# 04_HV_Bus_Sense.net
KiCad netlist of a schematic drawn in Altium Designer
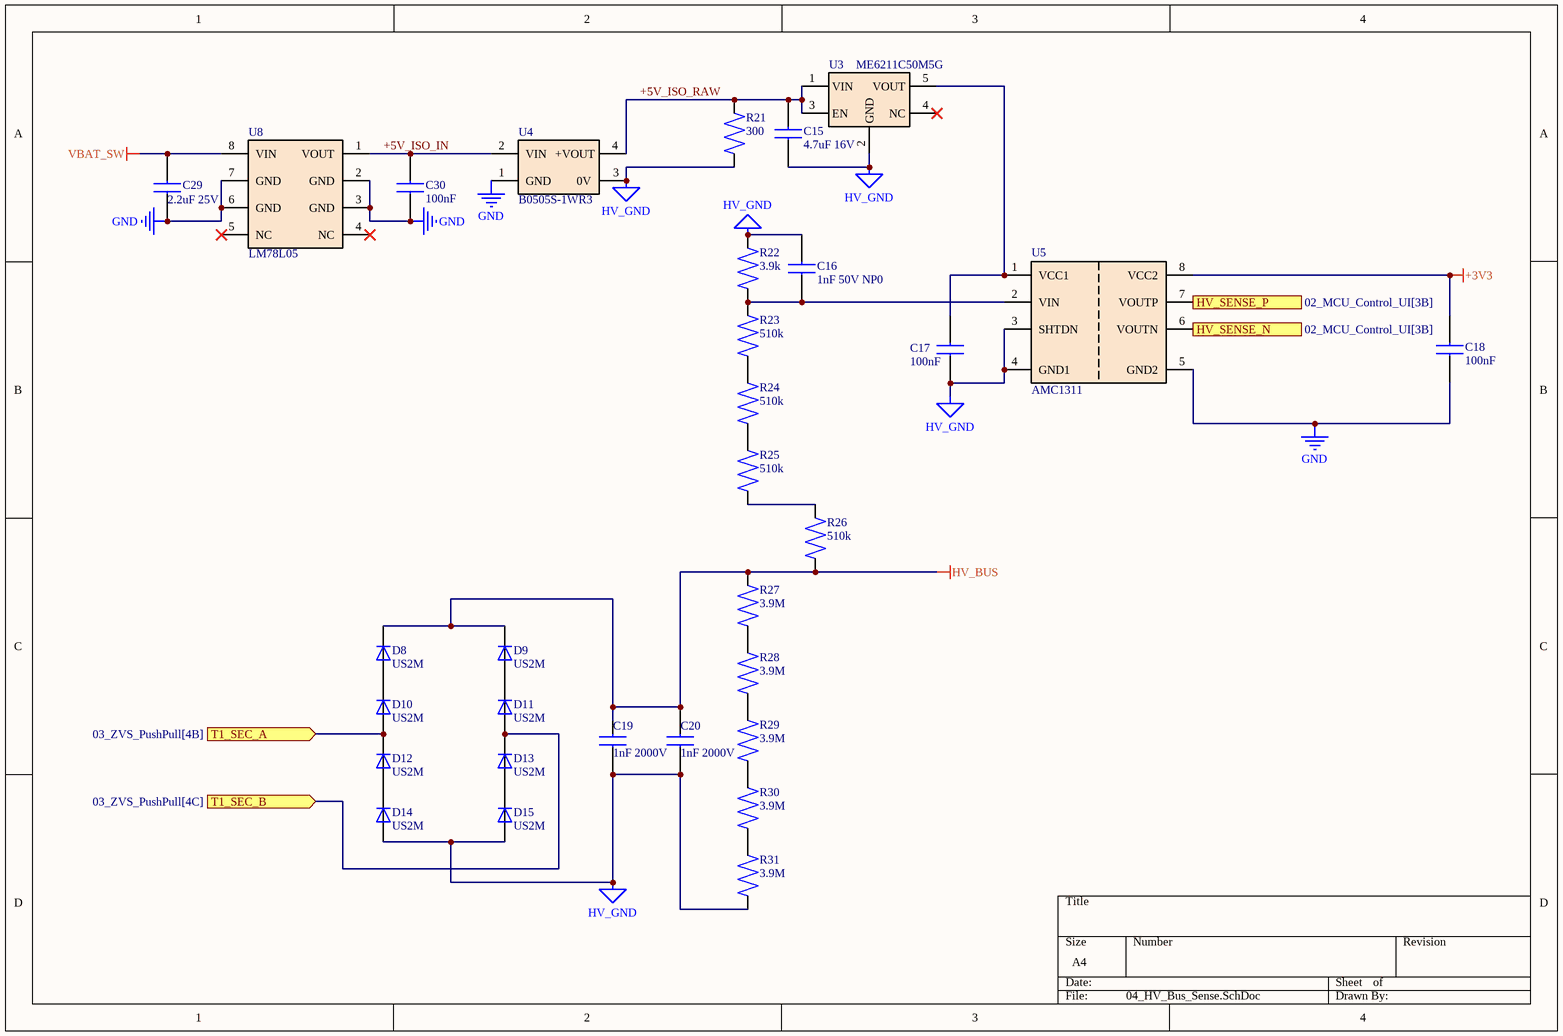
[diagram p0: 04_HV_Bus_Sense.SchDoc]

(export (version "E")
  (design (tool "Eeschema 10.0.6"))
  (components
    (comp (ref "C15")
      (value "4.7uF 16V")
      (footprint "CHIP_0805_SMD")
      (description "Capacitor MLCC, Ceramic, 4.7 uF, 16 V, ±10%, X7R, SMD 0805, Bypass / Decoupling, Samsung / Murata")
      (libsource (lib "Schlib1") (part "CAP_0805_4.7uF_16V_X7R"))
    )
    (comp (ref "C16")
      (value "1nF 50V NP0")
      (footprint "CHIP_0603_SMD")
      (libsource (lib "Schlib1") (part "CAP_0603_1nF_50V_NP0"))
    )
    (comp (ref "C17")
      (value "100nF")
      (footprint "CHIP_0603_SMD")
      (description "Capacitor MLCC, Ceramic, 100 nF, 50 V, ±10%, X7R, SMD 0603, Samsung Electro-Mechanics")
      (libsource (lib "Schlib1") (part "CAP_0603_100nF_50V_X7R"))
    )
    (comp (ref "C18")
      (value "100nF")
      (footprint "CHIP_0603_SMD")
      (description "Capacitor MLCC, Ceramic, 100 nF, 50 V, ±10%, X7R, SMD 0603, Samsung Electro-Mechanics")
      (libsource (lib "Schlib1") (part "CAP_0603_100nF_50V_X7R"))
    )
    (comp (ref "C19")
      (value "1nF 2000V")
      (footprint "CAP_FILM_P15.0_CBB81_HEAVY_DUTY")
      (libsource (lib "Schlib1") (part "CAP_FILM_CBB81_1nF_2000V"))
    )
    (comp (ref "C20")
      (value "1nF 2000V")
      (footprint "CAP_FILM_P15.0_CBB81_HEAVY_DUTY")
      (libsource (lib "Schlib1") (part "CAP_FILM_CBB81_1nF_2000V"))
    )
    (comp (ref "C29")
      (value "2.2uF 25V")
      (footprint "CHIP_0805_SMD")
      (description "Capacitor MLCC, Ceramic, 2.2 uF, 25 V, ±10%, X7R, SMD 0805, Hitano Enterprise")
      (libsource (lib "Schlib1") (part "CAP_0805_2.2uF_25V_X7R"))
    )
    (comp (ref "C30")
      (value "100nF")
      (footprint "CHIP_0603_SMD")
      (description "Capacitor MLCC, Ceramic, 100 nF, 50 V, ±10%, X7R, SMD 0603, Samsung Electro-Mechanics")
      (libsource (lib "Schlib1") (part "CAP_0603_100nF_50V_X7R"))
    )
    (comp (ref "D8")
      (value "US2M")
      (footprint "DIODE_DO-214AC_SMA")
      (description "Ultrafast High Voltage Surface Mount Rectifier, 1000V, 2A, trr=75ns, Vf=1.7V, SMA (DO-214AC)")
      (libsource (lib "Schlib1") (part "DIODE_ULTRAFAST_US2M_SMA"))
    )
    (comp (ref "D9")
      (value "US2M")
      (footprint "DIODE_DO-214AC_SMA")
      (description "Ultrafast High Voltage Surface Mount Rectifier, 1000V, 2A, trr=75ns, Vf=1.7V, SMA (DO-214AC)")
      (libsource (lib "Schlib1") (part "DIODE_ULTRAFAST_US2M_SMA"))
    )
    (comp (ref "D10")
      (value "US2M")
      (footprint "DIODE_DO-214AC_SMA")
      (description "Ultrafast High Voltage Surface Mount Rectifier, 1000V, 2A, trr=75ns, Vf=1.7V, SMA (DO-214AC)")
      (libsource (lib "Schlib1") (part "DIODE_ULTRAFAST_US2M_SMA"))
    )
    (comp (ref "D11")
      (value "US2M")
      (footprint "DIODE_DO-214AC_SMA")
      (description "Ultrafast High Voltage Surface Mount Rectifier, 1000V, 2A, trr=75ns, Vf=1.7V, SMA (DO-214AC)")
      (libsource (lib "Schlib1") (part "DIODE_ULTRAFAST_US2M_SMA"))
    )
    (comp (ref "D12")
      (value "US2M")
      (footprint "DIODE_DO-214AC_SMA")
      (description "Ultrafast High Voltage Surface Mount Rectifier, 1000V, 2A, trr=75ns, Vf=1.7V, SMA (DO-214AC)")
      (libsource (lib "Schlib1") (part "DIODE_ULTRAFAST_US2M_SMA"))
    )
    (comp (ref "D13")
      (value "US2M")
      (footprint "DIODE_DO-214AC_SMA")
      (description "Ultrafast High Voltage Surface Mount Rectifier, 1000V, 2A, trr=75ns, Vf=1.7V, SMA (DO-214AC)")
      (libsource (lib "Schlib1") (part "DIODE_ULTRAFAST_US2M_SMA"))
    )
    (comp (ref "D14")
      (value "US2M")
      (footprint "DIODE_DO-214AC_SMA")
      (description "Ultrafast High Voltage Surface Mount Rectifier, 1000V, 2A, trr=75ns, Vf=1.7V, SMA (DO-214AC)")
      (libsource (lib "Schlib1") (part "DIODE_ULTRAFAST_US2M_SMA"))
    )
    (comp (ref "D15")
      (value "US2M")
      (footprint "DIODE_DO-214AC_SMA")
      (description "Ultrafast High Voltage Surface Mount Rectifier, 1000V, 2A, trr=75ns, Vf=1.7V, SMA (DO-214AC)")
      (libsource (lib "Schlib1") (part "DIODE_ULTRAFAST_US2M_SMA"))
    )
    (comp (ref "R21")
      (value "300")
      (footprint "CHIP_0805_SMD")
      (description "Resistor, 300 Ohm, ±1%, 0.125W (1/8W), 150V, SMD 0805, Thick Film, Yageo")
      (libsource (lib "Schlib1") (part "RES_0805_300R_1%"))
    )
    (comp (ref "R22")
      (value "3.9k")
      (footprint "CHIP_0603_SMD")
      (description "Resistor, 3.9 kOhm, ±1%, 0.1W (1/10W), 75V, SMD 0603, Thick Film, Yageo")
      (libsource (lib "Schlib1") (part "RES_0603_3.9k_1%"))
    )
    (comp (ref "R23")
      (value "510k")
      (footprint "CHIP_1206_SMD")
      (description "Resistor, 510 kOhm, ±1%, 0.25W (1/4W), 200V, SMD 1206, High Voltage Divider, Thick Film, Yageo")
      (libsource (lib "Schlib1") (part "RES_1206_510k_1%"))
    )
    (comp (ref "R24")
      (value "510k")
      (footprint "CHIP_1206_SMD")
      (description "Resistor, 510 kOhm, ±1%, 0.25W (1/4W), 200V, SMD 1206, High Voltage Divider, Thick Film, Yageo")
      (libsource (lib "Schlib1") (part "RES_1206_510k_1%"))
    )
    (comp (ref "R25")
      (value "510k")
      (footprint "CHIP_1206_SMD")
      (description "Resistor, 510 kOhm, ±1%, 0.25W (1/4W), 200V, SMD 1206, High Voltage Divider, Thick Film, Yageo")
      (libsource (lib "Schlib1") (part "RES_1206_510k_1%"))
    )
    (comp (ref "R26")
      (value "510k")
      (footprint "CHIP_1206_SMD")
      (description "Resistor, 510 kOhm, ±1%, 0.25W (1/4W), 200V, SMD 1206, High Voltage Divider, Thick Film, Yageo")
      (libsource (lib "Schlib1") (part "RES_1206_510k_1%"))
    )
    (comp (ref "R27")
      (value "3.9M")
      (footprint "CHIP_1206_SMD")
      (libsource (lib "Schlib1") (part "RES_1206_3.9M_5%"))
    )
    (comp (ref "R28")
      (value "3.9M")
      (footprint "CHIP_1206_SMD")
      (libsource (lib "Schlib1") (part "RES_1206_3.9M_5%"))
    )
    (comp (ref "R29")
      (value "3.9M")
      (footprint "CHIP_1206_SMD")
      (libsource (lib "Schlib1") (part "RES_1206_3.9M_5%"))
    )
    (comp (ref "R30")
      (value "3.9M")
      (footprint "CHIP_1206_SMD")
      (libsource (lib "Schlib1") (part "RES_1206_3.9M_5%"))
    )
    (comp (ref "R31")
      (value "3.9M")
      (footprint "CHIP_1206_SMD")
      (libsource (lib "Schlib1") (part "RES_1206_3.9M_5%"))
    )
    (comp (ref "U3")
      (value "ME6211C50M5G")
      (footprint "SOT-23-5_M5_HANDSOLDER")
      (description "LDO Voltage Regulator, Fixed 5.0V, 500mA, Low Noise, High PSRR, SOT-23-5, Microne")
      (libsource (lib "Schlib1") (part "IC_REG_LDO_ME6211C50M5G"))
    )
    (comp (ref "U4")
      (value "B0505S-1WR3")
      (footprint "CONV_DC-DC_MORNSUN_SIP-4_11.6x6.0")
      (libsource (lib "Schlib1") (part "MODULE_DCDC_B0505S-1WR3"))
    )
    (comp (ref "U5")
      (value "AMC1311")
      (footprint "SOIC-8-DWV_WIDE_HANDSOLDER")
      (libsource (lib "Schlib1") (part "IC_ISO_AMP_AMC1311BDWVR"))
    )
    (comp (ref "U8")
      (value "LM78L05")
      (footprint "SOIC-8_1.27_4.9x3.9mm")
      (description "IC REG LINEAR 5V 100MA SOIC-8, Vin up to 30V")
      (libsource (lib "Schlib1") (part "MODULE_LDO_LM78L05_SO8"))
    )
  )
  (nets
    (net (code "1") (name "+3V3") (class "Default")
      (node (ref "C18") (pin "2") (pinfunction "2_2") (pintype "passive"))
      (node (ref "U5") (pin "8") (pinfunction "VCC2_8") (pintype "passive"))
    )
    (net (code "2") (name "/+5V_ISO_IN") (class "Default")
      (node (ref "C30") (pin "2") (pinfunction "2_2") (pintype "passive"))
      (node (ref "U4") (pin "2") (pinfunction "VIN_2") (pintype "passive"))
      (node (ref "U8") (pin "1") (pinfunction "VOUT_1") (pintype "passive"))
    )
    (net (code "3") (name "/+5V_ISO_RAW") (class "Default")
      (node (ref "C15") (pin "2") (pinfunction "2_2") (pintype "passive"))
      (node (ref "R21") (pin "2") (pinfunction "2_2") (pintype "passive"))
      (node (ref "U3") (pin "1") (pinfunction "VIN_1") (pintype "power_in"))
      (node (ref "U3") (pin "3") (pinfunction "EN_3") (pintype "passive"))
      (node (ref "U4") (pin "4") (pinfunction "+VOUT_4") (pintype "passive"))
    )
    (net (code "4") (name "/HV_SENSE_N") (class "Default")
      (node (ref "U5") (pin "6") (pinfunction "VOUTN_6") (pintype "passive"))
    )
    (net (code "5") (name "/HV_SENSE_P") (class "Default")
      (node (ref "U5") (pin "7") (pinfunction "VOUTP_7") (pintype "passive"))
    )
    (net (code "6") (name "/T1_SEC_A") (class "Default")
      (node (ref "D10") (pin "2") (pinfunction "A_2") (pintype "passive"))
      (node (ref "D12") (pin "1") (pinfunction "K_1") (pintype "passive"))
    )
    (net (code "7") (name "/T1_SEC_B") (class "Default")
      (node (ref "D11") (pin "2") (pinfunction "A_2") (pintype "passive"))
      (node (ref "D13") (pin "1") (pinfunction "K_1") (pintype "passive"))
    )
    (net (code "8") (name "GND") (class "Default")
      (node (ref "C18") (pin "1") (pinfunction "1_1") (pintype "passive"))
      (node (ref "C29") (pin "1") (pinfunction "1_1") (pintype "passive"))
      (node (ref "C30") (pin "1") (pinfunction "1_1") (pintype "passive"))
      (node (ref "U4") (pin "1") (pinfunction "GND_1") (pintype "power_in"))
      (node (ref "U5") (pin "5") (pinfunction "GND2_5") (pintype "passive"))
      (node (ref "U8") (pin "2") (pinfunction "GND_2") (pintype "passive"))
      (node (ref "U8") (pin "3") (pinfunction "GND_3") (pintype "passive"))
      (node (ref "U8") (pin "6") (pinfunction "GND_6") (pintype "passive"))
      (node (ref "U8") (pin "7") (pinfunction "GND_7") (pintype "passive"))
    )
    (net (code "9") (name "HV_BUS") (class "Default")
      (node (ref "C19") (pin "2") (pinfunction "2_2") (pintype "passive"))
      (node (ref "C20") (pin "2") (pinfunction "2_2") (pintype "passive"))
      (node (ref "D8") (pin "1") (pinfunction "K_1") (pintype "passive"))
      (node (ref "D9") (pin "1") (pinfunction "K_1") (pintype "passive"))
      (node (ref "R26") (pin "1") (pinfunction "1_1") (pintype "passive"))
      (node (ref "R27") (pin "2") (pinfunction "2_2") (pintype "passive"))
    )
    (net (code "10") (name "HV_GND") (class "Default")
      (node (ref "C15") (pin "1") (pinfunction "1_1") (pintype "passive"))
      (node (ref "C16") (pin "2") (pinfunction "2_2") (pintype "passive"))
      (node (ref "C17") (pin "1") (pinfunction "1_1") (pintype "passive"))
      (node (ref "C19") (pin "1") (pinfunction "1_1") (pintype "passive"))
      (node (ref "C20") (pin "1") (pinfunction "1_1") (pintype "passive"))
      (node (ref "D14") (pin "2") (pinfunction "A_2") (pintype "passive"))
      (node (ref "D15") (pin "2") (pinfunction "A_2") (pintype "passive"))
      (node (ref "R21") (pin "1") (pinfunction "1_1") (pintype "passive"))
      (node (ref "R22") (pin "2") (pinfunction "2_2") (pintype "passive"))
      (node (ref "R31") (pin "1") (pinfunction "1_1") (pintype "passive"))
      (node (ref "U3") (pin "2") (pinfunction "GND_2") (pintype "power_in"))
      (node (ref "U4") (pin "3") (pinfunction "0V_3") (pintype "passive"))
      (node (ref "U5") (pin "3") (pinfunction "SHTDN_3") (pintype "passive"))
      (node (ref "U5") (pin "4") (pinfunction "GND1_4") (pintype "passive"))
    )
    (net (code "11") (name "Net-(D10-K)") (class "Default")
      (node (ref "D10") (pin "1") (pinfunction "K_1") (pintype "passive"))
      (node (ref "D8") (pin "2") (pinfunction "A_2") (pintype "passive"))
    )
    (net (code "12") (name "Net-(D11-K)") (class "Default")
      (node (ref "D11") (pin "1") (pinfunction "K_1") (pintype "passive"))
      (node (ref "D9") (pin "2") (pinfunction "A_2") (pintype "passive"))
    )
    (net (code "13") (name "Net-(D12-A)") (class "Default")
      (node (ref "D12") (pin "2") (pinfunction "A_2") (pintype "passive"))
      (node (ref "D14") (pin "1") (pinfunction "K_1") (pintype "passive"))
    )
    (net (code "14") (name "Net-(D13-A)") (class "Default")
      (node (ref "D13") (pin "2") (pinfunction "A_2") (pintype "passive"))
      (node (ref "D15") (pin "1") (pinfunction "K_1") (pintype "passive"))
    )
    (net (code "15") (name "Net-(R23-Pad1)") (class "Default")
      (node (ref "R23") (pin "1") (pinfunction "1_1") (pintype "passive"))
      (node (ref "R24") (pin "2") (pinfunction "2_2") (pintype "passive"))
    )
    (net (code "16") (name "Net-(R24-Pad1)") (class "Default")
      (node (ref "R24") (pin "1") (pinfunction "1_1") (pintype "passive"))
      (node (ref "R25") (pin "2") (pinfunction "2_2") (pintype "passive"))
    )
    (net (code "17") (name "Net-(R25-Pad1)") (class "Default")
      (node (ref "R25") (pin "1") (pinfunction "1_1") (pintype "passive"))
      (node (ref "R26") (pin "2") (pinfunction "2_2") (pintype "passive"))
    )
    (net (code "18") (name "Net-(R27-Pad1)") (class "Default")
      (node (ref "R27") (pin "1") (pinfunction "1_1") (pintype "passive"))
      (node (ref "R28") (pin "2") (pinfunction "2_2") (pintype "passive"))
    )
    (net (code "19") (name "Net-(R28-Pad1)") (class "Default")
      (node (ref "R28") (pin "1") (pinfunction "1_1") (pintype "passive"))
      (node (ref "R29") (pin "2") (pinfunction "2_2") (pintype "passive"))
    )
    (net (code "20") (name "Net-(R29-Pad1)") (class "Default")
      (node (ref "R29") (pin "1") (pinfunction "1_1") (pintype "passive"))
      (node (ref "R30") (pin "2") (pinfunction "2_2") (pintype "passive"))
    )
    (net (code "21") (name "Net-(R30-Pad1)") (class "Default")
      (node (ref "R30") (pin "1") (pinfunction "1_1") (pintype "passive"))
      (node (ref "R31") (pin "2") (pinfunction "2_2") (pintype "passive"))
    )
    (net (code "22") (name "Net-(U3-VOUT)") (class "Default")
      (node (ref "C17") (pin "2") (pinfunction "2_2") (pintype "passive"))
      (node (ref "U3") (pin "5") (pinfunction "VOUT_5") (pintype "power_in"))
      (node (ref "U5") (pin "1") (pinfunction "VCC1_1") (pintype "passive"))
    )
    (net (code "23") (name "Net-(U5-VIN)") (class "Default")
      (node (ref "C16") (pin "1") (pinfunction "1_1") (pintype "passive"))
      (node (ref "R22") (pin "1") (pinfunction "1_1") (pintype "passive"))
      (node (ref "R23") (pin "2") (pinfunction "2_2") (pintype "passive"))
      (node (ref "U5") (pin "2") (pinfunction "VIN_2") (pintype "passive"))
    )
    (net (code "24") (name "VBAT_SW") (class "Default")
      (node (ref "C29") (pin "2") (pinfunction "2_2") (pintype "passive"))
      (node (ref "U8") (pin "8") (pinfunction "VIN_8") (pintype "passive"))
    )
    (net (code "25") (name "unconnected-(U3-NC-Pad4)") (class "Default")
      (node (ref "U3") (pin "4") (pinfunction "NC_4") (pintype "passive+no_connect"))
    )
    (net (code "26") (name "unconnected-(U8-NC-Pad4)") (class "Default")
      (node (ref "U8") (pin "4") (pinfunction "NC_4") (pintype "passive+no_connect"))
    )
    (net (code "27") (name "unconnected-(U8-NC-Pad5)") (class "Default")
      (node (ref "U8") (pin "5") (pinfunction "NC_5") (pintype "passive+no_connect"))
    )
  )
)
